# PRUC-Voltmeter_FPGA-Interface.net
KiCad netlist of a schematic drawn in Altium Designer
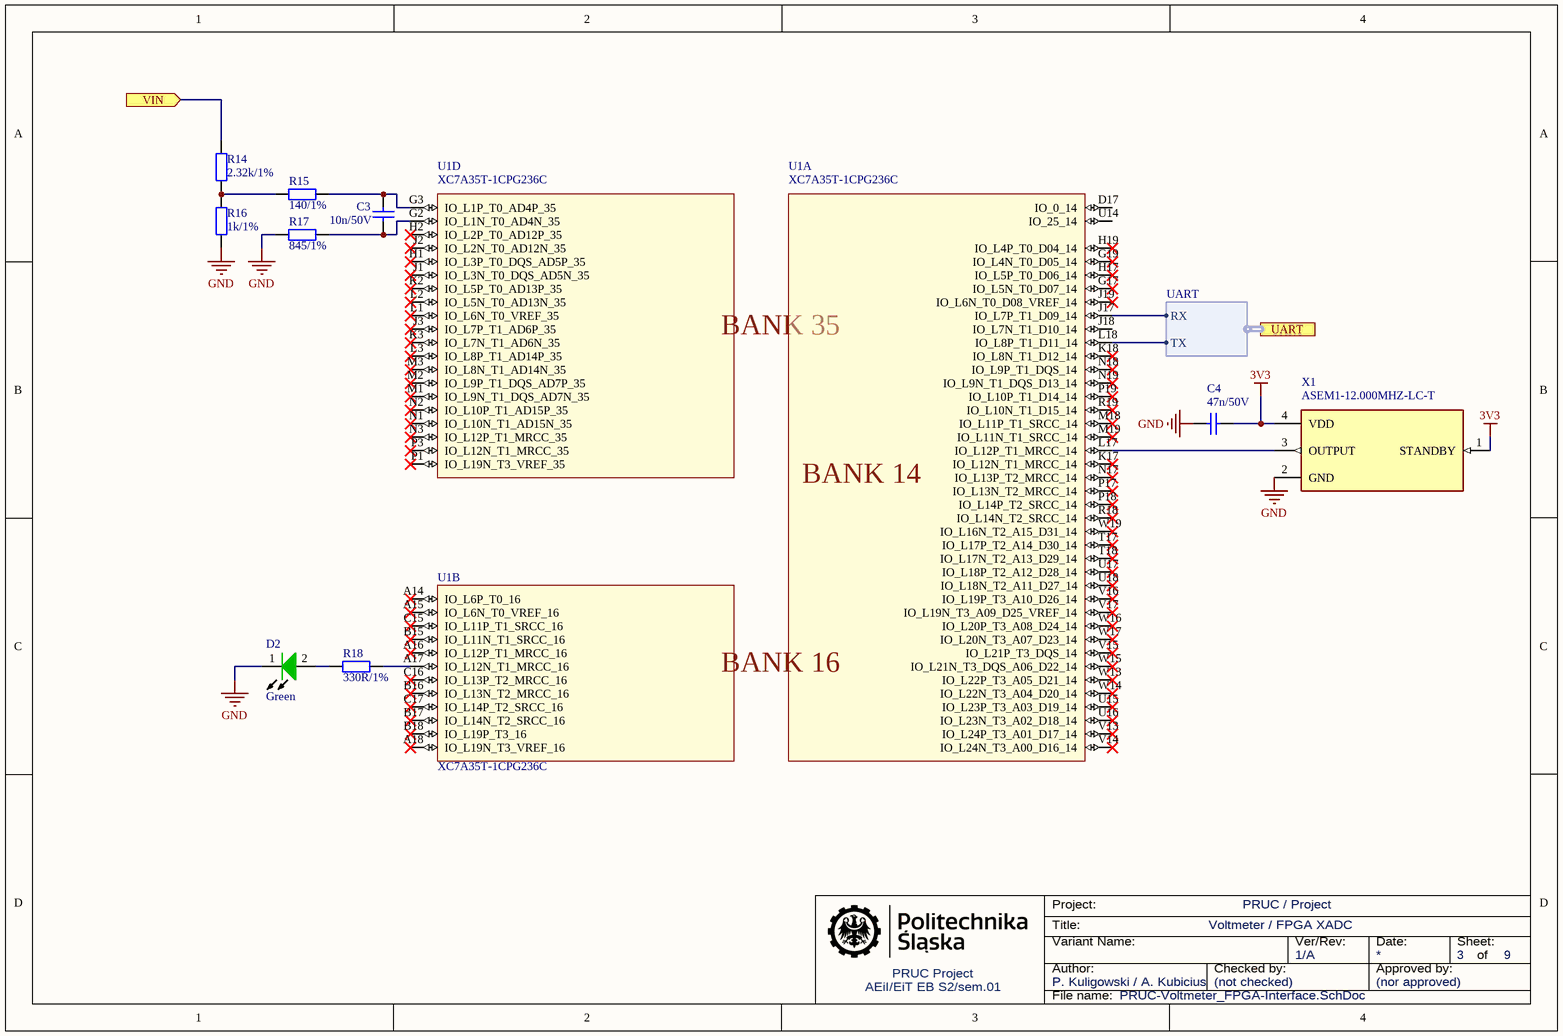
[diagram p0: PRUC-Voltmeter_FPGA-Interface.SchDoc]

(export (version "E")
  (design (tool "Eeschema 10.0.6"))
  (components
    (comp (ref "C3")
      (value "10n/50V")
      (footprint "MLCC_0603")
      (fields (field (name "PART NUMBER") "CL10B103KB8NNNC") (field (name "MANUFACTURER") "Samsung"))
      (libsource (lib "kplabs") (part "Cap"))
    )
    (comp (ref "C4")
      (value "47n/50V")
      (footprint "MLCC_0603")
      (fields (field (name "PART NUMBER") "CL10B473KB8NNNC") (field (name "MANUFACTURER") "Samsung"))
      (libsource (lib "kplabs") (part "Cap"))
    )
    (comp (ref "D2")
      (value "Green")
      (footprint "LED_0805_G")
      (fields (field (name "PART NUMBER") "OSG50805C1E") (field (name "MANUFACTURER") "OptoSupply"))
      (libsource (lib "kplabs") (part "LED_KA_G"))
    )
    (comp (ref "R14")
      (value "2.32k/1%")
      (footprint "R_0603")
      (fields (field (name "PART NUMBER") "0603SAF2201T5E") (field (name "MANUFACTURER") "Royalohm"))
      (libsource (lib "kplabs") (part "Res"))
    )
    (comp (ref "R15")
      (value "140/1%")
      (footprint "R_0603")
      (fields (field (name "PART NUMBER") "0603SAF2201T5E") (field (name "MANUFACTURER") "Royalohm"))
      (libsource (lib "") (part "Res_1"))
    )
    (comp (ref "R16")
      (value "1k/1%")
      (footprint "R_0603")
      (fields (field (name "PART NUMBER") "0603SAF1001T5E") (field (name "MANUFACTURER") "Royalohm"))
      (libsource (lib "kplabs") (part "Res"))
    )
    (comp (ref "R17")
      (value "845/1%")
      (footprint "R_0603")
      (fields (field (name "PART NUMBER") "0603SAF2201T5E") (field (name "MANUFACTURER") "Royalohm"))
      (libsource (lib "") (part "Res_1"))
    )
    (comp (ref "R18")
      (value "330R/1%")
      (footprint "R_0603")
      (fields (field (name "PART NUMBER") "0603SAF3300T5E") (field (name "MANUFACTURER") "Royalohm"))
      (libsource (lib "") (part "Res_2"))
    )
    (comp (ref "U1")
      (value "XC7A35T-1CPG236C")
      (footprint "CPG236-0.5mm")
      (fields (field (name "MANUFACTURER") "Xilinx"))
      (libsource (lib "") (part "XC7A35T-1CPG236C_1"))
    )
    (comp (ref "X1")
      (value "ASEM1-12.000MHZ-LC-T")
      (footprint "OSC_ASEM1-16.000MHZ-LC-T")
      (description "16MHz XO _Standard_ CMOS Oscillator 3.3V Standby _Power Down_ 4-SMD, No Lead")
      (fields (field (name "MF") "Abracon LLC") (field (name "MP") "ASEM1-16.000MHZ-LC-T"))
      (libsource (lib "ASEM1-16.000MHZ-LC-T") (part "ASEM1-16.000MHZ-LC-T"))
    )
  )
  (nets
    (net (code "2") (name "/RX") (class "Default")
      (node (ref "U1") (pin "J17") (pinfunction "IO_L7P_T1_D09_14_J17") (pintype "bidirectional"))
    )
    (net (code "3") (name "/TX") (class "Default")
      (node (ref "U1") (pin "L18") (pinfunction "IO_L8P_T1_D11_14_L18") (pintype "bidirectional"))
    )
    (net (code "4") (name "/VIN") (class "Default")
      (node (ref "R14") (pin "1") (pinfunction "1_1") (pintype "passive"))
    )
    (net (code "6") (name "3V3") (class "Default")
      (node (ref "C4") (pin "2") (pinfunction "2_2") (pintype "passive"))
      (node (ref "X1") (pin "1") (pinfunction "STANDBY_1") (pintype "input"))
      (node (ref "X1") (pin "4") (pinfunction "VDD_4") (pintype "power_in"))
    )
    (net (code "7") (name "GND") (class "Default")
      (node (ref "C4") (pin "1") (pinfunction "1_1") (pintype "passive"))
      (node (ref "D2") (pin "1") (pinfunction "K_1") (pintype "passive"))
      (node (ref "R16") (pin "2") (pinfunction "2_2") (pintype "passive"))
      (node (ref "R17") (pin "2") (pinfunction "2_2") (pintype "passive"))
      (node (ref "X1") (pin "2") (pinfunction "GND_2") (pintype "power_in"))
    )
    (net (code "8") (name "Net-(D2-A)") (class "Default")
      (node (ref "D2") (pin "2") (pinfunction "A_2") (pintype "passive"))
      (node (ref "R18") (pin "1") (pinfunction "1_1") (pintype "passive"))
    )
    (net (code "9") (name "Net-(R14-Pad2)") (class "Default")
      (node (ref "R14") (pin "2") (pinfunction "2_2") (pintype "passive"))
      (node (ref "R15") (pin "2") (pinfunction "2_2") (pintype "passive"))
      (node (ref "R16") (pin "1") (pinfunction "1_1") (pintype "passive"))
    )
    (net (code "10") (name "Net-(U1A-IO_L12P_T1_MRCC_14)") (class "Default")
      (node (ref "U1") (pin "L17") (pinfunction "IO_L12P_T1_MRCC_14_L17") (pintype "bidirectional"))
      (node (ref "X1") (pin "3") (pinfunction "OUTPUT_3") (pintype "output"))
    )
    (net (code "11") (name "Net-(U1B-IO_L12N_T1_MRCC_16)") (class "Default")
      (node (ref "R18") (pin "2") (pinfunction "2_2") (pintype "passive"))
      (node (ref "U1") (pin "A17") (pinfunction "IO_L12N_T1_MRCC_16_A17") (pintype "bidirectional"))
    )
    (net (code "12") (name "Net-(U1D-IO_L1N_T0_AD4N_35)") (class "Default")
      (node (ref "C3") (pin "2") (pinfunction "2_2") (pintype "passive"))
      (node (ref "R17") (pin "1") (pinfunction "1_1") (pintype "passive"))
      (node (ref "U1") (pin "G2") (pinfunction "IO_L1N_T0_AD4N_35_G2") (pintype "bidirectional"))
    )
    (net (code "13") (name "Net-(U1D-IO_L1P_T0_AD4P_35)") (class "Default")
      (node (ref "C3") (pin "1") (pinfunction "1_1") (pintype "passive"))
      (node (ref "R15") (pin "1") (pinfunction "1_1") (pintype "passive"))
      (node (ref "U1") (pin "G3") (pinfunction "IO_L1P_T0_AD4P_35_G3") (pintype "bidirectional"))
    )
    (net (code "14") (name "unconnected-(U1A-IO_0_14-PadD17)") (class "Default")
      (node (ref "U1") (pin "D17") (pinfunction "IO_0_14_D17") (pintype "bidirectional"))
    )
    (net (code "15") (name "unconnected-(U1A-IO_25_14-PadU14)") (class "Default")
      (node (ref "U1") (pin "U14") (pinfunction "IO_25_14_U14") (pintype "bidirectional"))
    )
    (net (code "16") (name "unconnected-(U1A-IO_L4N_T0_D05_14-PadG19)") (class "Default")
      (node (ref "U1") (pin "G19") (pinfunction "IO_L4N_T0_D05_14_G19") (pintype "bidirectional+no_connect"))
    )
    (net (code "17") (name "unconnected-(U1A-IO_L4P_T0_D04_14-PadH19)") (class "Default")
      (node (ref "U1") (pin "H19") (pinfunction "IO_L4P_T0_D04_14_H19") (pintype "bidirectional+no_connect"))
    )
    (net (code "18") (name "unconnected-(U1A-IO_L5N_T0_D07_14-PadG17)") (class "Default")
      (node (ref "U1") (pin "G17") (pinfunction "IO_L5N_T0_D07_14_G17") (pintype "bidirectional+no_connect"))
    )
    (net (code "19") (name "unconnected-(U1A-IO_L5P_T0_D06_14-PadH17)") (class "Default")
      (node (ref "U1") (pin "H17") (pinfunction "IO_L5P_T0_D06_14_H17") (pintype "bidirectional+no_connect"))
    )
    (net (code "20") (name "unconnected-(U1A-IO_L6N_T0_D08_VREF_14-PadJ19)") (class "Default")
      (node (ref "U1") (pin "J19") (pinfunction "IO_L6N_T0_D08_VREF_14_J19") (pintype "bidirectional+no_connect"))
    )
    (net (code "21") (name "unconnected-(U1A-IO_L7N_T1_D10_14-PadJ18)") (class "Default")
      (node (ref "U1") (pin "J18") (pinfunction "IO_L7N_T1_D10_14_J18") (pintype "bidirectional"))
    )
    (net (code "22") (name "unconnected-(U1A-IO_L8N_T1_D12_14-PadK18)") (class "Default")
      (node (ref "U1") (pin "K18") (pinfunction "IO_L8N_T1_D12_14_K18") (pintype "bidirectional+no_connect"))
    )
    (net (code "23") (name "unconnected-(U1A-IO_L9N_T1_DQS_D13_14-PadN19)") (class "Default")
      (node (ref "U1") (pin "N19") (pinfunction "IO_L9N_T1_DQS_D13_14_N19") (pintype "bidirectional+no_connect"))
    )
    (net (code "24") (name "unconnected-(U1A-IO_L9P_T1_DQS_14-PadN18)") (class "Default")
      (node (ref "U1") (pin "N18") (pinfunction "IO_L9P_T1_DQS_14_N18") (pintype "bidirectional+no_connect"))
    )
    (net (code "25") (name "unconnected-(U1A-IO_L10N_T1_D15_14-PadR19)") (class "Default")
      (node (ref "U1") (pin "R19") (pinfunction "IO_L10N_T1_D15_14_R19") (pintype "bidirectional+no_connect"))
    )
    (net (code "26") (name "unconnected-(U1A-IO_L10P_T1_D14_14-PadP19)") (class "Default")
      (node (ref "U1") (pin "P19") (pinfunction "IO_L10P_T1_D14_14_P19") (pintype "bidirectional+no_connect"))
    )
    (net (code "27") (name "unconnected-(U1A-IO_L11N_T1_SRCC_14-PadM19)") (class "Default")
      (node (ref "U1") (pin "M19") (pinfunction "IO_L11N_T1_SRCC_14_M19") (pintype "bidirectional+no_connect"))
    )
    (net (code "28") (name "unconnected-(U1A-IO_L11P_T1_SRCC_14-PadM18)") (class "Default")
      (node (ref "U1") (pin "M18") (pinfunction "IO_L11P_T1_SRCC_14_M18") (pintype "bidirectional+no_connect"))
    )
    (net (code "29") (name "unconnected-(U1A-IO_L12N_T1_MRCC_14-PadK17)") (class "Default")
      (node (ref "U1") (pin "K17") (pinfunction "IO_L12N_T1_MRCC_14_K17") (pintype "bidirectional+no_connect"))
    )
    (net (code "30") (name "unconnected-(U1A-IO_L13N_T2_MRCC_14-PadP17)") (class "Default")
      (node (ref "U1") (pin "P17") (pinfunction "IO_L13N_T2_MRCC_14_P17") (pintype "bidirectional+no_connect"))
    )
    (net (code "31") (name "unconnected-(U1A-IO_L13P_T2_MRCC_14-PadN17)") (class "Default")
      (node (ref "U1") (pin "N17") (pinfunction "IO_L13P_T2_MRCC_14_N17") (pintype "bidirectional+no_connect"))
    )
    (net (code "32") (name "unconnected-(U1A-IO_L14N_T2_SRCC_14-PadR18)") (class "Default")
      (node (ref "U1") (pin "R18") (pinfunction "IO_L14N_T2_SRCC_14_R18") (pintype "bidirectional+no_connect"))
    )
    (net (code "33") (name "unconnected-(U1A-IO_L14P_T2_SRCC_14-PadP18)") (class "Default")
      (node (ref "U1") (pin "P18") (pinfunction "IO_L14P_T2_SRCC_14_P18") (pintype "bidirectional+no_connect"))
    )
    (net (code "34") (name "unconnected-(U1A-IO_L16N_T2_A15_D31_14-PadW19)") (class "Default")
      (node (ref "U1") (pin "W19") (pinfunction "IO_L16N_T2_A15_D31_14_W19") (pintype "bidirectional+no_connect"))
    )
    (net (code "35") (name "unconnected-(U1A-IO_L17N_T2_A13_D29_14-PadT18)") (class "Default")
      (node (ref "U1") (pin "T18") (pinfunction "IO_L17N_T2_A13_D29_14_T18") (pintype "bidirectional+no_connect"))
    )
    (net (code "36") (name "unconnected-(U1A-IO_L17P_T2_A14_D30_14-PadT17)") (class "Default")
      (node (ref "U1") (pin "T17") (pinfunction "IO_L17P_T2_A14_D30_14_T17") (pintype "bidirectional+no_connect"))
    )
    (net (code "37") (name "unconnected-(U1A-IO_L18N_T2_A11_D27_14-PadU18)") (class "Default")
      (node (ref "U1") (pin "U18") (pinfunction "IO_L18N_T2_A11_D27_14_U18") (pintype "bidirectional+no_connect"))
    )
    (net (code "38") (name "unconnected-(U1A-IO_L18P_T2_A12_D28_14-PadU17)") (class "Default")
      (node (ref "U1") (pin "U17") (pinfunction "IO_L18P_T2_A12_D28_14_U17") (pintype "bidirectional+no_connect"))
    )
    (net (code "39") (name "unconnected-(U1A-IO_L19N_T3_A09_D25_VREF_14-PadV17)") (class "Default")
      (node (ref "U1") (pin "V17") (pinfunction "IO_L19N_T3_A09_D25_VREF_14_V17") (pintype "bidirectional+no_connect"))
    )
    (net (code "40") (name "unconnected-(U1A-IO_L19P_T3_A10_D26_14-PadV16)") (class "Default")
      (node (ref "U1") (pin "V16") (pinfunction "IO_L19P_T3_A10_D26_14_V16") (pintype "bidirectional+no_connect"))
    )
    (net (code "41") (name "unconnected-(U1A-IO_L20N_T3_A07_D23_14-PadW17)") (class "Default")
      (node (ref "U1") (pin "W17") (pinfunction "IO_L20N_T3_A07_D23_14_W17") (pintype "bidirectional+no_connect"))
    )
    (net (code "42") (name "unconnected-(U1A-IO_L20P_T3_A08_D24_14-PadW16)") (class "Default")
      (node (ref "U1") (pin "W16") (pinfunction "IO_L20P_T3_A08_D24_14_W16") (pintype "bidirectional+no_connect"))
    )
    (net (code "43") (name "unconnected-(U1A-IO_L21N_T3_DQS_A06_D22_14-PadW15)") (class "Default")
      (node (ref "U1") (pin "W15") (pinfunction "IO_L21N_T3_DQS_A06_D22_14_W15") (pintype "bidirectional+no_connect"))
    )
    (net (code "44") (name "unconnected-(U1A-IO_L21P_T3_DQS_14-PadV15)") (class "Default")
      (node (ref "U1") (pin "V15") (pinfunction "IO_L21P_T3_DQS_14_V15") (pintype "bidirectional+no_connect"))
    )
    (net (code "45") (name "unconnected-(U1A-IO_L22N_T3_A04_D20_14-PadW14)") (class "Default")
      (node (ref "U1") (pin "W14") (pinfunction "IO_L22N_T3_A04_D20_14_W14") (pintype "bidirectional+no_connect"))
    )
    (net (code "46") (name "unconnected-(U1A-IO_L22P_T3_A05_D21_14-PadW13)") (class "Default")
      (node (ref "U1") (pin "W13") (pinfunction "IO_L22P_T3_A05_D21_14_W13") (pintype "bidirectional+no_connect"))
    )
    (net (code "47") (name "unconnected-(U1A-IO_L23N_T3_A02_D18_14-PadU16)") (class "Default")
      (node (ref "U1") (pin "U16") (pinfunction "IO_L23N_T3_A02_D18_14_U16") (pintype "bidirectional+no_connect"))
    )
    (net (code "48") (name "unconnected-(U1A-IO_L23P_T3_A03_D19_14-PadU15)") (class "Default")
      (node (ref "U1") (pin "U15") (pinfunction "IO_L23P_T3_A03_D19_14_U15") (pintype "bidirectional+no_connect"))
    )
    (net (code "49") (name "unconnected-(U1A-IO_L24N_T3_A00_D16_14-PadV14)") (class "Default")
      (node (ref "U1") (pin "V14") (pinfunction "IO_L24N_T3_A00_D16_14_V14") (pintype "bidirectional+no_connect"))
    )
    (net (code "50") (name "unconnected-(U1A-IO_L24P_T3_A01_D17_14-PadV13)") (class "Default")
      (node (ref "U1") (pin "V13") (pinfunction "IO_L24P_T3_A01_D17_14_V13") (pintype "bidirectional+no_connect"))
    )
    (net (code "51") (name "unconnected-(U1B-IO_L6N_T0_VREF_16-PadA15)") (class "Default")
      (node (ref "U1") (pin "A15") (pinfunction "IO_L6N_T0_VREF_16_A15") (pintype "bidirectional+no_connect"))
    )
    (net (code "52") (name "unconnected-(U1B-IO_L6P_T0_16-PadA14)") (class "Default")
      (node (ref "U1") (pin "A14") (pinfunction "IO_L6P_T0_16_A14") (pintype "bidirectional+no_connect"))
    )
    (net (code "53") (name "unconnected-(U1B-IO_L11N_T1_SRCC_16-PadB15)") (class "Default")
      (node (ref "U1") (pin "B15") (pinfunction "IO_L11N_T1_SRCC_16_B15") (pintype "bidirectional+no_connect"))
    )
    (net (code "54") (name "unconnected-(U1B-IO_L11P_T1_SRCC_16-PadC15)") (class "Default")
      (node (ref "U1") (pin "C15") (pinfunction "IO_L11P_T1_SRCC_16_C15") (pintype "bidirectional+no_connect"))
    )
    (net (code "55") (name "unconnected-(U1B-IO_L12P_T1_MRCC_16-PadA16)") (class "Default")
      (node (ref "U1") (pin "A16") (pinfunction "IO_L12P_T1_MRCC_16_A16") (pintype "bidirectional+no_connect"))
    )
    (net (code "56") (name "unconnected-(U1B-IO_L13N_T2_MRCC_16-PadB16)") (class "Default")
      (node (ref "U1") (pin "B16") (pinfunction "IO_L13N_T2_MRCC_16_B16") (pintype "bidirectional+no_connect"))
    )
    (net (code "57") (name "unconnected-(U1B-IO_L13P_T2_MRCC_16-PadC16)") (class "Default")
      (node (ref "U1") (pin "C16") (pinfunction "IO_L13P_T2_MRCC_16_C16") (pintype "bidirectional+no_connect"))
    )
    (net (code "58") (name "unconnected-(U1B-IO_L14N_T2_SRCC_16-PadB17)") (class "Default")
      (node (ref "U1") (pin "B17") (pinfunction "IO_L14N_T2_SRCC_16_B17") (pintype "bidirectional+no_connect"))
    )
    (net (code "59") (name "unconnected-(U1B-IO_L14P_T2_SRCC_16-PadC17)") (class "Default")
      (node (ref "U1") (pin "C17") (pinfunction "IO_L14P_T2_SRCC_16_C17") (pintype "bidirectional+no_connect"))
    )
    (net (code "60") (name "unconnected-(U1B-IO_L19N_T3_VREF_16-PadA18)") (class "Default")
      (node (ref "U1") (pin "A18") (pinfunction "IO_L19N_T3_VREF_16_A18") (pintype "bidirectional+no_connect"))
    )
    (net (code "61") (name "unconnected-(U1B-IO_L19P_T3_16-PadB18)") (class "Default")
      (node (ref "U1") (pin "B18") (pinfunction "IO_L19P_T3_16_B18") (pintype "bidirectional+no_connect"))
    )
    (net (code "62") (name "unconnected-(U1D-IO_L2N_T0_AD12N_35-PadJ2)") (class "Default")
      (node (ref "U1") (pin "J2") (pinfunction "IO_L2N_T0_AD12N_35_J2") (pintype "bidirectional+no_connect"))
    )
    (net (code "63") (name "unconnected-(U1D-IO_L2P_T0_AD12P_35-PadH2)") (class "Default")
      (node (ref "U1") (pin "H2") (pinfunction "IO_L2P_T0_AD12P_35_H2") (pintype "bidirectional+no_connect"))
    )
    (net (code "64") (name "unconnected-(U1D-IO_L3N_T0_DQS_AD5N_35-PadJ1)") (class "Default")
      (node (ref "U1") (pin "J1") (pinfunction "IO_L3N_T0_DQS_AD5N_35_J1") (pintype "bidirectional+no_connect"))
    )
    (net (code "65") (name "unconnected-(U1D-IO_L3P_T0_DQS_AD5P_35-PadH1)") (class "Default")
      (node (ref "U1") (pin "H1") (pinfunction "IO_L3P_T0_DQS_AD5P_35_H1") (pintype "bidirectional+no_connect"))
    )
    (net (code "66") (name "unconnected-(U1D-IO_L5N_T0_AD13N_35-PadL2)") (class "Default")
      (node (ref "U1") (pin "L2") (pinfunction "IO_L5N_T0_AD13N_35_L2") (pintype "bidirectional+no_connect"))
    )
    (net (code "67") (name "unconnected-(U1D-IO_L5P_T0_AD13P_35-PadK2)") (class "Default")
      (node (ref "U1") (pin "K2") (pinfunction "IO_L5P_T0_AD13P_35_K2") (pintype "bidirectional+no_connect"))
    )
    (net (code "68") (name "unconnected-(U1D-IO_L6N_T0_VREF_35-PadL1)") (class "Default")
      (node (ref "U1") (pin "L1") (pinfunction "IO_L6N_T0_VREF_35_L1") (pintype "bidirectional+no_connect"))
    )
    (net (code "69") (name "unconnected-(U1D-IO_L7N_T1_AD6N_35-PadK3)") (class "Default")
      (node (ref "U1") (pin "K3") (pinfunction "IO_L7N_T1_AD6N_35_K3") (pintype "bidirectional+no_connect"))
    )
    (net (code "70") (name "unconnected-(U1D-IO_L7P_T1_AD6P_35-PadJ3)") (class "Default")
      (node (ref "U1") (pin "J3") (pinfunction "IO_L7P_T1_AD6P_35_J3") (pintype "bidirectional+no_connect"))
    )
    (net (code "71") (name "unconnected-(U1D-IO_L8N_T1_AD14N_35-PadM3)") (class "Default")
      (node (ref "U1") (pin "M3") (pinfunction "IO_L8N_T1_AD14N_35_M3") (pintype "bidirectional+no_connect"))
    )
    (net (code "72") (name "unconnected-(U1D-IO_L8P_T1_AD14P_35-PadL3)") (class "Default")
      (node (ref "U1") (pin "L3") (pinfunction "IO_L8P_T1_AD14P_35_L3") (pintype "bidirectional+no_connect"))
    )
    (net (code "73") (name "unconnected-(U1D-IO_L9N_T1_DQS_AD7N_35-PadM1)") (class "Default")
      (node (ref "U1") (pin "M1") (pinfunction "IO_L9N_T1_DQS_AD7N_35_M1") (pintype "bidirectional+no_connect"))
    )
    (net (code "74") (name "unconnected-(U1D-IO_L9P_T1_DQS_AD7P_35-PadM2)") (class "Default")
      (node (ref "U1") (pin "M2") (pinfunction "IO_L9P_T1_DQS_AD7P_35_M2") (pintype "bidirectional+no_connect"))
    )
    (net (code "75") (name "unconnected-(U1D-IO_L10N_T1_AD15N_35-PadN1)") (class "Default")
      (node (ref "U1") (pin "N1") (pinfunction "IO_L10N_T1_AD15N_35_N1") (pintype "bidirectional+no_connect"))
    )
    (net (code "76") (name "unconnected-(U1D-IO_L10P_T1_AD15P_35-PadN2)") (class "Default")
      (node (ref "U1") (pin "N2") (pinfunction "IO_L10P_T1_AD15P_35_N2") (pintype "bidirectional+no_connect"))
    )
    (net (code "77") (name "unconnected-(U1D-IO_L12N_T1_MRCC_35-PadP3)") (class "Default")
      (node (ref "U1") (pin "P3") (pinfunction "IO_L12N_T1_MRCC_35_P3") (pintype "bidirectional+no_connect"))
    )
    (net (code "78") (name "unconnected-(U1D-IO_L12P_T1_MRCC_35-PadN3)") (class "Default")
      (node (ref "U1") (pin "N3") (pinfunction "IO_L12P_T1_MRCC_35_N3") (pintype "bidirectional+no_connect"))
    )
    (net (code "79") (name "unconnected-(U1D-IO_L19N_T3_VREF_35-PadP1)") (class "Default")
      (node (ref "U1") (pin "P1") (pinfunction "IO_L19N_T3_VREF_35_P1") (pintype "bidirectional+no_connect"))
    )
  )
)
